# ESP8266-Thing-Dev.net
KiCad netlist of a schematic drawn in EAGLE
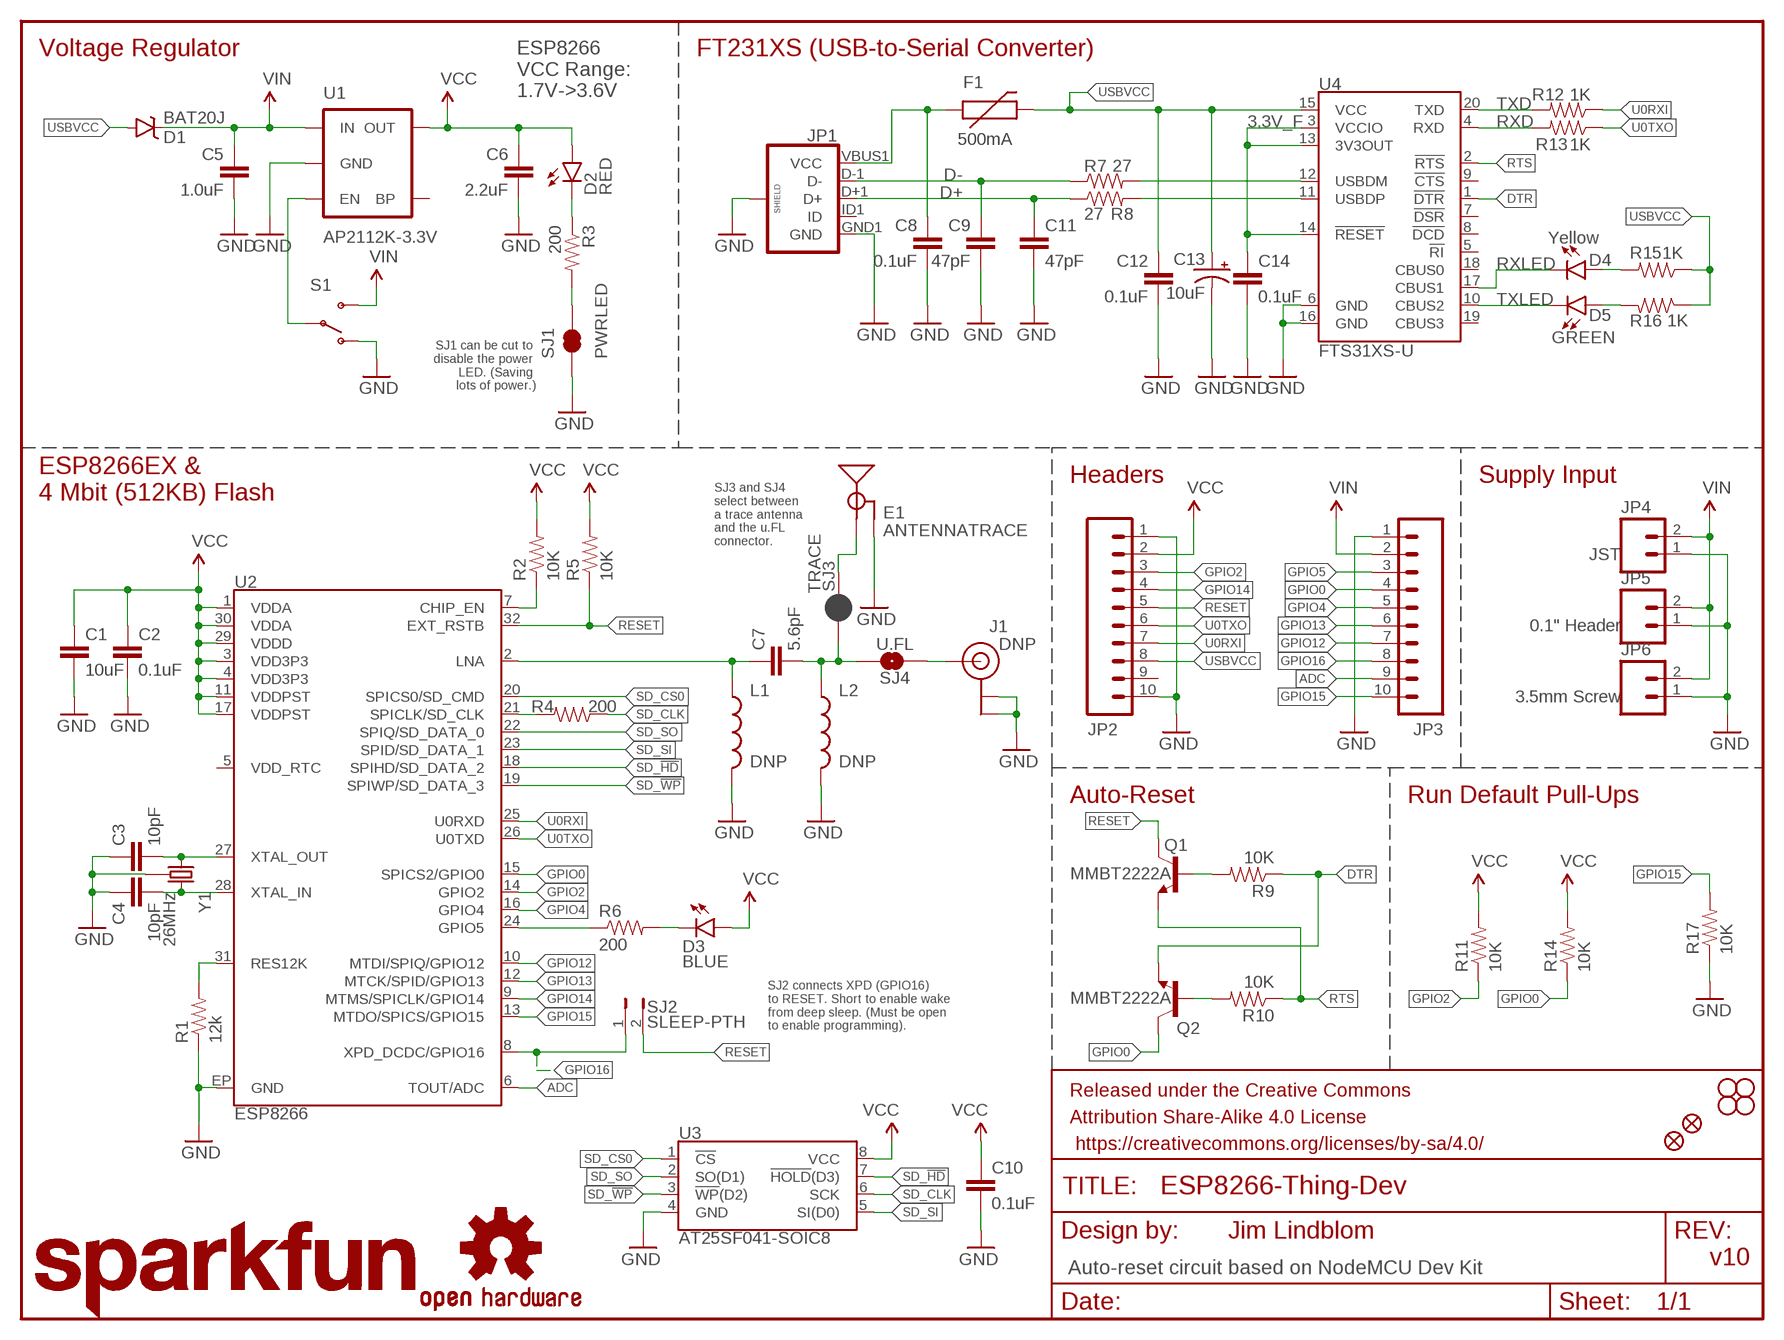
[diagram p0: schematic, sheet 1]

(export (version "E")
  (design (tool "Eeschema 10.0.6"))
  (components
    (comp (ref "C1")
      (value "10uF")
      (footprint "eagle-import:0603-CAP")
      (libsource (lib "eagle-import") (part "10UF-6.3V-20%(0603)"))
    )
    (comp (ref "C2")
      (value "0.1uF")
      (footprint "eagle-import:0603-CAP")
      (libsource (lib "eagle-import") (part "0.1UF-25V(+80/-20%)(0603)"))
    )
    (comp (ref "C3")
      (value "10pF")
      (footprint "eagle-import:0603-CAP")
      (libsource (lib "eagle-import") (part "10PF-50V-5%(0603)"))
    )
    (comp (ref "C4")
      (value "10pF")
      (footprint "eagle-import:0603-CAP")
      (libsource (lib "eagle-import") (part "10PF-50V-5%(0603)"))
    )
    (comp (ref "C5")
      (value "1.0uF")
      (footprint "eagle-import:0805")
      (libsource (lib "eagle-import") (part "1.0UF-25V-+80/-20(0805)"))
    )
    (comp (ref "C6")
      (value "2.2uF")
      (footprint "eagle-import:0603-CAP")
      (libsource (lib "eagle-import") (part "2.2UF-10V-20%(0603)"))
    )
    (comp (ref "C7")
      (value "5.6pF")
      (footprint "eagle-import:0603-CAP")
      (libsource (lib "eagle-import") (part "CAP0603-CAP"))
    )
    (comp (ref "C8")
      (value "0.1uF")
      (footprint "eagle-import:0603-CAP")
      (libsource (lib "eagle-import") (part "0.1UF-25V(+80/-20%)(0603)"))
    )
    (comp (ref "C9")
      (value "47pF")
      (footprint "eagle-import:0603-CAP")
      (libsource (lib "eagle-import") (part "47PF-50V-5%(0603)"))
    )
    (comp (ref "C10")
      (value "0.1uF")
      (footprint "eagle-import:0603-CAP")
      (libsource (lib "eagle-import") (part "0.1UF-25V(+80/-20%)(0603)"))
    )
    (comp (ref "C11")
      (value "47pF")
      (footprint "eagle-import:0603-CAP")
      (libsource (lib "eagle-import") (part "47PF-50V-5%(0603)"))
    )
    (comp (ref "C12")
      (value "0.1uF")
      (footprint "eagle-import:0603-CAP")
      (libsource (lib "eagle-import") (part "0.1UF-25V(+80/-20%)(0603)"))
    )
    (comp (ref "C13")
      (value "10uF")
      (footprint "eagle-import:EIA3216")
      (libsource (lib "eagle-import") (part "10UF-16V-10%(TANT)"))
    )
    (comp (ref "C14")
      (value "0.1uF")
      (footprint "eagle-import:0603-CAP")
      (libsource (lib "eagle-import") (part "0.1UF-25V(+80/-20%)(0603)"))
    )
    (comp (ref "D1")
      (value "BAT20J")
      (footprint "eagle-import:SOD-323")
      (libsource (lib "eagle-import") (part "DIODE-SCHOTTKY-BAT20J"))
    )
    (comp (ref "D2")
      (value "RED")
      (footprint "eagle-import:LED-0603")
      (libsource (lib "eagle-import") (part "LED-RED0603"))
    )
    (comp (ref "D3")
      (value "BLUE")
      (footprint "eagle-import:LED-0603")
      (libsource (lib "eagle-import") (part "LED-BLUE0603"))
    )
    (comp (ref "D4")
      (value "Yellow")
      (footprint "eagle-import:LED-0603")
      (libsource (lib "eagle-import") (part "LED-YELLOW0603"))
    )
    (comp (ref "D5")
      (value "GREEN")
      (footprint "eagle-import:LED-0603")
      (libsource (lib "eagle-import") (part "LED-GREEN0603"))
    )
    (comp (ref "E1")
      (value "ANTENNATRACE")
      (footprint "eagle-import:TRACE_ANTENNA_2.4GHZ_25.7MM")
      (libsource (lib "eagle-import") (part "ANTENNATRACE"))
    )
    (comp (ref "F1")
      (value "500mA")
      (footprint "eagle-import:PTC-1206")
      (libsource (lib "eagle-import") (part "PTCSMD"))
    )
    (comp (ref "FID1")
      (value "FIDUCIAL1X2")
      (footprint "eagle-import:FIDUCIAL-1X2")
      (libsource (lib "eagle-import") (part "FIDUCIAL1X2"))
    )
    (comp (ref "FID2")
      (value "FIDUCIAL1X2")
      (footprint "eagle-import:FIDUCIAL-1X2")
      (libsource (lib "eagle-import") (part "FIDUCIAL1X2"))
    )
    (comp (ref "FRAME1")
      (value "FRAME-LETTER")
      (footprint "eagle-import:CREATIVE_COMMONS")
      (libsource (lib "eagle-import") (part "FRAME-LETTER"))
    )
    (comp (ref "J1")
      (value "DNP")
      (footprint "eagle-import:U.FL")
      (libsource (lib "eagle-import") (part "U.FL"))
    )
    (comp (ref "JP1")
      (value "USB_MICROB_PLUGCONN-11752")
      (footprint "eagle-import:USB-B-MICRO-SMD_V03")
      (libsource (lib "eagle-import") (part "USB_MICROB_PLUGCONN-11752"))
    )
    (comp (ref "JP2")
      (value "M10NO_SILK_PTH_FEMALE")
      (footprint "eagle-import:1X10_NO_SILK")
      (libsource (lib "eagle-import") (part "M10NO_SILK_PTH_FEMALE"))
    )
    (comp (ref "JP3")
      (value "M10NO_SILK_PTH_FEMALE")
      (footprint "eagle-import:1X10_NO_SILK")
      (libsource (lib "eagle-import") (part "M10NO_SILK_PTH_FEMALE"))
    )
    (comp (ref "JP4")
      (value "M02JST-PTH-2")
      (footprint "eagle-import:JST-2-PTH")
      (libsource (lib "eagle-import") (part "M02JST-PTH-2"))
    )
    (comp (ref "JP5")
      (value "M021X02_NO_SILK")
      (footprint "eagle-import:1X02_NO_SILK")
      (libsource (lib "eagle-import") (part "M021X02_NO_SILK"))
    )
    (comp (ref "JP6")
      (value "M023.5MM-NO_SILK")
      (footprint "eagle-import:SCREWTERMINAL-3.5MM-2-NS")
      (libsource (lib "eagle-import") (part "M023.5MM-NO_SILK"))
    )
    (comp (ref "L1")
      (value "DNP")
      (footprint "eagle-import:0603")
      (libsource (lib "eagle-import") (part "INDUCTOR0603"))
    )
    (comp (ref "L2")
      (value "DNP")
      (footprint "eagle-import:0603")
      (libsource (lib "eagle-import") (part "INDUCTOR0603"))
    )
    (comp (ref "LOGO1")
      (value "SFE_LOGO_NAME.2_INCH")
      (footprint "eagle-import:SFE_LOGO_NAME_.2")
      (libsource (lib "eagle-import") (part "SFE_LOGO_NAME.2_INCH"))
    )
    (comp (ref "LOGO2")
      (value "OSHW-LOGOS")
      (footprint "eagle-import:OSHW-LOGO-S")
      (libsource (lib "eagle-import") (part "OSHW-LOGOS"))
    )
    (comp (ref "Q1")
      (value "MMBT2222A")
      (footprint "eagle-import:SOT23-3")
      (libsource (lib "eagle-import") (part "TRANSISTOR_NPNMMBT2222A"))
    )
    (comp (ref "Q2")
      (value "MMBT2222A")
      (footprint "eagle-import:SOT23-3")
      (libsource (lib "eagle-import") (part "TRANSISTOR_NPNMMBT2222A"))
    )
    (comp (ref "R1")
      (value "12k")
      (footprint "eagle-import:0603-RES")
      (libsource (lib "eagle-import") (part "12KOHM-1/10W-1%(0603)"))
    )
    (comp (ref "R2")
      (value "10K")
      (footprint "eagle-import:0603-RES")
      (libsource (lib "eagle-import") (part "10KOHM1/10W1%(0603)0603"))
    )
    (comp (ref "R3")
      (value "200")
      (footprint "eagle-import:0603-RES")
      (libsource (lib "eagle-import") (part "200OHM1/10W1%(0603)"))
    )
    (comp (ref "R4")
      (value "200")
      (footprint "eagle-import:0603-RES")
      (libsource (lib "eagle-import") (part "200OHM1/10W1%(0603)"))
    )
    (comp (ref "R5")
      (value "10K")
      (footprint "eagle-import:0603-RES")
      (libsource (lib "eagle-import") (part "10KOHM1/10W1%(0603)0603"))
    )
    (comp (ref "R6")
      (value "200")
      (footprint "eagle-import:0603-RES")
      (libsource (lib "eagle-import") (part "200OHM1/10W1%(0603)"))
    )
    (comp (ref "R7")
      (value "27")
      (footprint "eagle-import:0603-RES")
      (libsource (lib "eagle-import") (part "27OHM1/10W1%(0603)0603-RES"))
    )
    (comp (ref "R8")
      (value "27")
      (footprint "eagle-import:0603-RES")
      (libsource (lib "eagle-import") (part "27OHM1/10W1%(0603)0603-RES"))
    )
    (comp (ref "R9")
      (value "10K")
      (footprint "eagle-import:0603-RES")
      (libsource (lib "eagle-import") (part "10KOHM1/10W1%(0603)0603"))
    )
    (comp (ref "R10")
      (value "10K")
      (footprint "eagle-import:0603-RES")
      (libsource (lib "eagle-import") (part "10KOHM1/10W1%(0603)0603"))
    )
    (comp (ref "R11")
      (value "10K")
      (footprint "eagle-import:0603-RES")
      (libsource (lib "eagle-import") (part "10KOHM1/10W1%(0603)0603"))
    )
    (comp (ref "R12")
      (value "1K")
      (footprint "eagle-import:0603-RES")
      (libsource (lib "eagle-import") (part "1KOHM-1/10W-1%(0603)"))
    )
    (comp (ref "R13")
      (value "1K")
      (footprint "eagle-import:0603-RES")
      (libsource (lib "eagle-import") (part "1KOHM-1/10W-1%(0603)"))
    )
    (comp (ref "R14")
      (value "10K")
      (footprint "eagle-import:0603-RES")
      (libsource (lib "eagle-import") (part "10KOHM1/10W1%(0603)0603"))
    )
    (comp (ref "R15")
      (value "1K")
      (footprint "eagle-import:0603-RES")
      (libsource (lib "eagle-import") (part "1KOHM-1/10W-1%(0603)"))
    )
    (comp (ref "R16")
      (value "1K")
      (footprint "eagle-import:0603-RES")
      (libsource (lib "eagle-import") (part "1KOHM-1/10W-1%(0603)"))
    )
    (comp (ref "R17")
      (value "10K")
      (footprint "eagle-import:0603-RES")
      (libsource (lib "eagle-import") (part "10KOHM1/10W1%(0603)0603"))
    )
    (comp (ref "S1")
      (value "SWITCH-SPDT-SMD-A")
      (footprint "eagle-import:SWITCH-SPST-SMD-A")
      (libsource (lib "eagle-import") (part "SWITCH-SPDT-SMD-A"))
    )
    (comp (ref "SJ1")
      (value "PWRLED")
      (footprint "eagle-import:PAD-JUMPER-2-NC_BY_TRACE_YES_SILK")
      (libsource (lib "eagle-import") (part "JUMPER-PAD-2-NC_BY_TRACE"))
    )
    (comp (ref "SJ2")
      (value "SLEEP-PTH")
      (footprint "eagle-import:PTH-JUMPER-2-NO_NO_SILK")
      (libsource (lib "eagle-import") (part "JUMPER-PTH-2-NO"))
    )
    (comp (ref "SJ3")
      (value "TRACE")
      (footprint "eagle-import:PAD-JUMPER-2-NC_BY_PASTE_NO_SILK")
      (libsource (lib "eagle-import") (part "JUMPER-PAD-2-NC_BY_PASTENO-SILK"))
    )
    (comp (ref "SJ4")
      (value "U.FL")
      (footprint "eagle-import:PAD-JUMPER-2-NO_NO_SILK")
      (libsource (lib "eagle-import") (part "JUMPER-PAD-2-NO"))
    )
    (comp (ref "STANDOFF1")
      (value "STAND-OFF")
      (footprint "eagle-import:STAND-OFF")
      (libsource (lib "eagle-import") (part "STAND-OFF"))
    )
    (comp (ref "STANDOFF2")
      (value "STAND-OFF")
      (footprint "eagle-import:STAND-OFF")
      (libsource (lib "eagle-import") (part "STAND-OFF"))
    )
    (comp (ref "STANDOFF3")
      (value "STAND-OFF")
      (footprint "eagle-import:STAND-OFF")
      (libsource (lib "eagle-import") (part "STAND-OFF"))
    )
    (comp (ref "STANDOFF4")
      (value "STAND-OFF")
      (footprint "eagle-import:STAND-OFF")
      (libsource (lib "eagle-import") (part "STAND-OFF"))
    )
    (comp (ref "U1")
      (value "AP2112K-3.3V")
      (footprint "eagle-import:SOT23-5")
      (libsource (lib "eagle-import") (part "V_REG_LDOSMD"))
    )
    (comp (ref "U2")
      (value "ESP8266")
      (footprint "eagle-import:QFN32")
      (libsource (lib "eagle-import") (part "ESP8266"))
    )
    (comp (ref "U3")
      (value "AT25SF041-SOIC8")
      (footprint "eagle-import:SO08")
      (libsource (lib "eagle-import") (part "AT25SF041-SOIC8"))
    )
    (comp (ref "U4")
      (value "FTS31XS-U")
      (footprint "eagle-import:SSOP20_L")
      (libsource (lib "eagle-import") (part "FT231XS"))
    )
    (comp (ref "Y1")
      (value "26MHz")
      (footprint "eagle-import:CRYSTAL-SMD-3.2X2.5")
      (libsource (lib "eagle-import") (part "CRYSTAL-GROUNDED3.2X2.5"))
    )
  )
  (nets
    (net (code "1") (name "/3.3V_F") (class "Default")
      (node (ref "C14") (pin "1") (pinfunction "1_1") (pintype "passive"))
      (node (ref "U4") (pin "13") (pinfunction "3V3OUT_13") (pintype "bidirectional"))
      (node (ref "U4") (pin "14") (pinfunction "~{RESET}_14") (pintype "bidirectional"))
      (node (ref "U4") (pin "3") (pinfunction "VCCIO_3") (pintype "bidirectional"))
    )
    (net (code "2") (name "/D+") (class "Default")
      (node (ref "C11") (pin "1") (pinfunction "1_1") (pintype "passive"))
      (node (ref "JP1") (pin "D+1") (pinfunction "D+_D+1") (pintype "bidirectional"))
      (node (ref "R8") (pin "1") (pinfunction "1_1") (pintype "passive"))
    )
    (net (code "3") (name "/D-") (class "Default")
      (node (ref "C9") (pin "1") (pinfunction "1_1") (pintype "passive"))
      (node (ref "JP1") (pin "D-1") (pinfunction "D-_D-1") (pintype "bidirectional"))
      (node (ref "R7") (pin "1") (pinfunction "1_1") (pintype "passive"))
    )
    (net (code "4") (name "/RXD") (class "Default")
      (node (ref "R13") (pin "2") (pinfunction "2_2") (pintype "passive"))
      (node (ref "U4") (pin "4") (pinfunction "RXD_4") (pintype "bidirectional"))
    )
    (net (code "5") (name "/RXLED") (class "Default")
      (node (ref "D4") (pin "C") (pinfunction "C_C") (pintype "passive"))
      (node (ref "U4") (pin "17") (pinfunction "CBUS1_17") (pintype "bidirectional"))
    )
    (net (code "6") (name "/SD_~{HD}") (class "Default")
      (node (ref "U2") (pin "18") (pinfunction "SPIHD/SD_DATA_2_18") (pintype "bidirectional"))
      (node (ref "U3") (pin "7") (pinfunction "~{HOLD}(D3)_7") (pintype "bidirectional"))
    )
    (net (code "7") (name "/SD_~{WP}") (class "Default")
      (node (ref "U2") (pin "19") (pinfunction "SPIWP/SD_DATA_3_19") (pintype "bidirectional"))
      (node (ref "U3") (pin "3") (pinfunction "~{WP}(D2)_3") (pintype "bidirectional"))
    )
    (net (code "8") (name "/TXD") (class "Default")
      (node (ref "R12") (pin "2") (pinfunction "2_2") (pintype "passive"))
      (node (ref "U4") (pin "20") (pinfunction "TXD_20") (pintype "bidirectional"))
    )
    (net (code "9") (name "/TXLED") (class "Default")
      (node (ref "D5") (pin "C") (pinfunction "C_C") (pintype "passive"))
      (node (ref "U4") (pin "10") (pinfunction "CBUS2_10") (pintype "bidirectional"))
    )
    (net (code "10") (name "ADC") (class "Default")
      (node (ref "JP3") (pin "9") (pinfunction "9_9") (pintype "passive"))
      (node (ref "U2") (pin "6") (pinfunction "TOUT/ADC_6") (pintype "bidirectional"))
    )
    (net (code "11") (name "DTR") (class "Default")
      (node (ref "Q2") (pin "2") (pinfunction "E_2") (pintype "passive"))
      (node (ref "R9") (pin "1") (pinfunction "1_1") (pintype "passive"))
      (node (ref "U4") (pin "1") (pinfunction "~{DTR}_1") (pintype "bidirectional"))
    )
    (net (code "12") (name "GND") (class "Default")
      (node (ref "C1") (pin "2") (pinfunction "2_2") (pintype "passive"))
      (node (ref "C10") (pin "2") (pinfunction "2_2") (pintype "passive"))
      (node (ref "C11") (pin "2") (pinfunction "2_2") (pintype "passive"))
      (node (ref "C12") (pin "2") (pinfunction "2_2") (pintype "passive"))
      (node (ref "C13") (pin "C") (pinfunction "-_C") (pintype "passive"))
      (node (ref "C14") (pin "2") (pinfunction "2_2") (pintype "passive"))
      (node (ref "C2") (pin "2") (pinfunction "2_2") (pintype "passive"))
      (node (ref "C3") (pin "1") (pinfunction "1_1") (pintype "passive"))
      (node (ref "C4") (pin "1") (pinfunction "1_1") (pintype "passive"))
      (node (ref "C5") (pin "2") (pinfunction "2_2") (pintype "passive"))
      (node (ref "C6") (pin "2") (pinfunction "2_2") (pintype "passive"))
      (node (ref "C8") (pin "2") (pinfunction "2_2") (pintype "passive"))
      (node (ref "C9") (pin "2") (pinfunction "2_2") (pintype "passive"))
      (node (ref "E1") (pin "GND") (pinfunction "GND_GND") (pintype "bidirectional"))
      (node (ref "E1") (pin "GND2") (pinfunction "GND_GND2") (pintype "bidirectional"))
      (node (ref "J1") (pin "P$1") (pinfunction "GND_P$1") (pintype "bidirectional"))
      (node (ref "J1") (pin "P$2") (pinfunction "GND_P$2") (pintype "bidirectional"))
      (node (ref "JP1") (pin "GND1") (pinfunction "GND_GND1") (pintype "bidirectional"))
      (node (ref "JP1") (pin "SHIELD1") (pinfunction "SHIELD_SHIELD1") (pintype "bidirectional"))
      (node (ref "JP1") (pin "SHIELD2") (pinfunction "SHIELD_SHIELD2") (pintype "bidirectional"))
      (node (ref "JP1") (pin "SHIELD3") (pinfunction "SHIELD_SHIELD3") (pintype "bidirectional"))
      (node (ref "JP2") (pin "1") (pinfunction "1_1") (pintype "passive"))
      (node (ref "JP2") (pin "10") (pinfunction "10_10") (pintype "passive"))
      (node (ref "JP3") (pin "1") (pinfunction "1_1") (pintype "passive"))
      (node (ref "JP4") (pin "1") (pinfunction "1_1") (pintype "passive"))
      (node (ref "JP5") (pin "1") (pinfunction "1_1") (pintype "passive"))
      (node (ref "JP6") (pin "1") (pinfunction "1_1") (pintype "passive"))
      (node (ref "L1") (pin "2") (pinfunction "2_2") (pintype "passive"))
      (node (ref "L2") (pin "2") (pinfunction "2_2") (pintype "passive"))
      (node (ref "R1") (pin "1") (pinfunction "1_1") (pintype "passive"))
      (node (ref "R17") (pin "1") (pinfunction "1_1") (pintype "passive"))
      (node (ref "S1") (pin "1") (pinfunction "O_1") (pintype "passive"))
      (node (ref "SJ1") (pin "1") (pinfunction "1_1") (pintype "passive"))
      (node (ref "U1") (pin "2") (pinfunction "GND_2") (pintype "input"))
      (node (ref "U2") (pin "EP") (pinfunction "GND_EP") (pintype "bidirectional"))
      (node (ref "U3") (pin "4") (pinfunction "GND_4") (pintype "bidirectional"))
      (node (ref "U4") (pin "16") (pinfunction "GND_16") (pintype "bidirectional"))
      (node (ref "U4") (pin "6") (pinfunction "GND_6") (pintype "bidirectional"))
      (node (ref "Y1") (pin "2") (pinfunction "GND_2") (pintype "passive"))
      (node (ref "Y1") (pin "4") (pinfunction "GND_4") (pintype "passive"))
    )
    (net (code "13") (name "GPIO0") (class "Default")
      (node (ref "JP3") (pin "4") (pinfunction "4_4") (pintype "passive"))
      (node (ref "Q2") (pin "3") (pinfunction "C_3") (pintype "passive"))
      (node (ref "R14") (pin "1") (pinfunction "1_1") (pintype "passive"))
      (node (ref "U2") (pin "15") (pinfunction "SPICS2/GPIO0_15") (pintype "bidirectional"))
    )
    (net (code "14") (name "GPIO2") (class "Default")
      (node (ref "JP2") (pin "3") (pinfunction "3_3") (pintype "passive"))
      (node (ref "R11") (pin "1") (pinfunction "1_1") (pintype "passive"))
      (node (ref "U2") (pin "14") (pinfunction "GPIO2_14") (pintype "bidirectional"))
    )
    (net (code "15") (name "GPIO4") (class "Default")
      (node (ref "JP3") (pin "5") (pinfunction "5_5") (pintype "passive"))
      (node (ref "U2") (pin "16") (pinfunction "GPIO4_16") (pintype "bidirectional"))
    )
    (net (code "16") (name "GPIO5") (class "Default")
      (node (ref "JP3") (pin "3") (pinfunction "3_3") (pintype "passive"))
      (node (ref "R6") (pin "1") (pinfunction "1_1") (pintype "passive"))
      (node (ref "U2") (pin "24") (pinfunction "GPIO5_24") (pintype "bidirectional"))
    )
    (net (code "17") (name "GPIO12") (class "Default")
      (node (ref "JP3") (pin "7") (pinfunction "7_7") (pintype "passive"))
      (node (ref "U2") (pin "10") (pinfunction "MTDI/SPIQ/GPIO12_10") (pintype "bidirectional"))
    )
    (net (code "18") (name "GPIO13") (class "Default")
      (node (ref "JP3") (pin "6") (pinfunction "6_6") (pintype "passive"))
      (node (ref "U2") (pin "12") (pinfunction "MTCK/SPID/GPIO13_12") (pintype "bidirectional"))
    )
    (net (code "19") (name "GPIO14") (class "Default")
      (node (ref "JP2") (pin "4") (pinfunction "4_4") (pintype "passive"))
      (node (ref "U2") (pin "9") (pinfunction "MTMS/SPICLK/GPIO14_9") (pintype "bidirectional"))
    )
    (net (code "20") (name "GPIO15") (class "Default")
      (node (ref "JP3") (pin "10") (pinfunction "10_10") (pintype "passive"))
      (node (ref "R17") (pin "2") (pinfunction "2_2") (pintype "passive"))
      (node (ref "U2") (pin "13") (pinfunction "MTDO/SPICS/GPIO15_13") (pintype "bidirectional"))
    )
    (net (code "21") (name "GPIO16") (class "Default")
      (node (ref "JP3") (pin "8") (pinfunction "8_8") (pintype "passive"))
      (node (ref "SJ2") (pin "1") (pinfunction "1_1") (pintype "passive"))
      (node (ref "U2") (pin "8") (pinfunction "XPD_DCDC/GPIO16_8") (pintype "bidirectional"))
    )
    (net (code "22") (name "Net-(C7-Pad2)") (class "Default")
      (node (ref "C7") (pin "2") (pinfunction "2_2") (pintype "passive"))
      (node (ref "L2") (pin "1") (pinfunction "1_1") (pintype "passive"))
      (node (ref "SJ3") (pin "1") (pinfunction "1_1") (pintype "passive"))
      (node (ref "SJ4") (pin "2") (pinfunction "2_2") (pintype "passive"))
    )
    (net (code "23") (name "Net-(D2-PadC)") (class "Default")
      (node (ref "D2") (pin "C") (pinfunction "C_C") (pintype "passive"))
      (node (ref "R3") (pin "1") (pinfunction "1_1") (pintype "passive"))
    )
    (net (code "24") (name "Net-(D3-PadC)") (class "Default")
      (node (ref "D3") (pin "C") (pinfunction "C_C") (pintype "passive"))
      (node (ref "R6") (pin "2") (pinfunction "2_2") (pintype "passive"))
    )
    (net (code "25") (name "Net-(D4-PadA)") (class "Default")
      (node (ref "D4") (pin "A") (pinfunction "A_A") (pintype "passive"))
      (node (ref "R15") (pin "2") (pinfunction "2_2") (pintype "passive"))
    )
    (net (code "26") (name "Net-(D5-PadA)") (class "Default")
      (node (ref "D5") (pin "A") (pinfunction "A_A") (pintype "passive"))
      (node (ref "R16") (pin "2") (pinfunction "2_2") (pintype "passive"))
    )
    (net (code "27") (name "Net-(E1-SIGNAL)") (class "Default")
      (node (ref "E1") (pin "ANT") (pinfunction "SIGNAL_ANT") (pintype "bidirectional"))
      (node (ref "SJ3") (pin "2") (pinfunction "2_2") (pintype "passive"))
    )
    (net (code "28") (name "Net-(J1-SIGNAL)") (class "Default")
      (node (ref "J1") (pin "P$3") (pinfunction "SIGNAL_P$3") (pintype "bidirectional"))
      (node (ref "SJ4") (pin "1") (pinfunction "1_1") (pintype "passive"))
    )
    (net (code "29") (name "Net-(JP1-VCC)") (class "Default")
      (node (ref "C8") (pin "1") (pinfunction "1_1") (pintype "passive"))
      (node (ref "F1") (pin "1") (pinfunction "1_1") (pintype "bidirectional"))
      (node (ref "JP1") (pin "VBUS1") (pinfunction "VCC_VBUS1") (pintype "bidirectional"))
    )
    (net (code "30") (name "Net-(Q1-B)") (class "Default")
      (node (ref "Q1") (pin "1") (pinfunction "B_1") (pintype "passive"))
      (node (ref "R9") (pin "2") (pinfunction "2_2") (pintype "passive"))
    )
    (net (code "31") (name "Net-(Q2-B)") (class "Default")
      (node (ref "Q2") (pin "1") (pinfunction "B_1") (pintype "passive"))
      (node (ref "R10") (pin "2") (pinfunction "2_2") (pintype "passive"))
    )
    (net (code "32") (name "Net-(R3-Pad2)") (class "Default")
      (node (ref "R3") (pin "2") (pinfunction "2_2") (pintype "passive"))
      (node (ref "SJ1") (pin "2") (pinfunction "2_2") (pintype "passive"))
    )
    (net (code "33") (name "Net-(S1-P)") (class "Default")
      (node (ref "S1") (pin "2") (pinfunction "P_2") (pintype "passive"))
      (node (ref "U1") (pin "3") (pinfunction "EN_3") (pintype "input"))
    )
    (net (code "34") (name "Net-(U2-CHIP_EN)") (class "Default")
      (node (ref "R2") (pin "1") (pinfunction "1_1") (pintype "passive"))
      (node (ref "U2") (pin "7") (pinfunction "CHIP_EN_7") (pintype "bidirectional"))
    )
    (net (code "35") (name "Net-(U2-LNA)") (class "Default")
      (node (ref "C7") (pin "1") (pinfunction "1_1") (pintype "passive"))
      (node (ref "L1") (pin "1") (pinfunction "1_1") (pintype "passive"))
      (node (ref "U2") (pin "2") (pinfunction "LNA_2") (pintype "bidirectional"))
    )
    (net (code "36") (name "Net-(U2-RES12K)") (class "Default")
      (node (ref "R1") (pin "2") (pinfunction "2_2") (pintype "passive"))
      (node (ref "U2") (pin "31") (pinfunction "RES12K_31") (pintype "bidirectional"))
    )
    (net (code "37") (name "Net-(U2-SPICLK{slash}SD_CLK)") (class "Default")
      (node (ref "R4") (pin "2") (pinfunction "2_2") (pintype "passive"))
      (node (ref "U2") (pin "21") (pinfunction "SPICLK/SD_CLK_21") (pintype "bidirectional"))
    )
    (net (code "38") (name "Net-(U2-XTAL_IN)") (class "Default")
      (node (ref "C4") (pin "2") (pinfunction "2_2") (pintype "passive"))
      (node (ref "U2") (pin "28") (pinfunction "XTAL_IN_28") (pintype "bidirectional"))
      (node (ref "Y1") (pin "3") (pinfunction "2_3") (pintype "passive"))
    )
    (net (code "39") (name "Net-(U2-XTAL_OUT)") (class "Default")
      (node (ref "C3") (pin "2") (pinfunction "2_2") (pintype "passive"))
      (node (ref "U2") (pin "27") (pinfunction "XTAL_OUT_27") (pintype "bidirectional"))
      (node (ref "Y1") (pin "1") (pinfunction "1_1") (pintype "passive"))
    )
    (net (code "40") (name "Net-(U4-USBDM)") (class "Default")
      (node (ref "R7") (pin "2") (pinfunction "2_2") (pintype "passive"))
      (node (ref "U4") (pin "12") (pinfunction "USBDM_12") (pintype "bidirectional"))
    )
    (net (code "41") (name "Net-(U4-USBDP)") (class "Default")
      (node (ref "R8") (pin "2") (pinfunction "2_2") (pintype "passive"))
      (node (ref "U4") (pin "11") (pinfunction "USBDP_11") (pintype "bidirectional"))
    )
    (net (code "42") (name "RESET") (class "Default")
      (node (ref "JP2") (pin "5") (pinfunction "5_5") (pintype "passive"))
      (node (ref "Q1") (pin "3") (pinfunction "C_3") (pintype "passive"))
      (node (ref "R5") (pin "1") (pinfunction "1_1") (pintype "passive"))
      (node (ref "SJ2") (pin "2") (pinfunction "2_2") (pintype "passive"))
      (node (ref "U2") (pin "32") (pinfunction "EXT_RSTB_32") (pintype "bidirectional"))
    )
    (net (code "43") (name "RTS") (class "Default")
      (node (ref "Q1") (pin "2") (pinfunction "E_2") (pintype "passive"))
      (node (ref "R10") (pin "1") (pinfunction "1_1") (pintype "passive"))
      (node (ref "U4") (pin "2") (pinfunction "~{RTS}_2") (pintype "bidirectional"))
    )
    (net (code "44") (name "SD_CLK") (class "Default")
      (node (ref "R4") (pin "1") (pinfunction "1_1") (pintype "passive"))
      (node (ref "U3") (pin "6") (pinfunction "SCK_6") (pintype "bidirectional"))
    )
    (net (code "45") (name "SD_CS0") (class "Default")
      (node (ref "U2") (pin "20") (pinfunction "SPICS0/SD_CMD_20") (pintype "bidirectional"))
      (node (ref "U3") (pin "1") (pinfunction "~{CS}_1") (pintype "bidirectional"))
    )
    (net (code "46") (name "SD_SI") (class "Default")
      (node (ref "U2") (pin "23") (pinfunction "SPID/SD_DATA_1_23") (pintype "bidirectional"))
      (node (ref "U3") (pin "5") (pinfunction "SI(D0)_5") (pintype "bidirectional"))
    )
    (net (code "47") (name "SD_SO") (class "Default")
      (node (ref "U2") (pin "22") (pinfunction "SPIQ/SD_DATA_0_22") (pintype "bidirectional"))
      (node (ref "U3") (pin "2") (pinfunction "SO(D1)_2") (pintype "bidirectional"))
    )
    (net (code "48") (name "U0RXI") (class "Default")
      (node (ref "JP2") (pin "7") (pinfunction "7_7") (pintype "passive"))
      (node (ref "R12") (pin "1") (pinfunction "1_1") (pintype "passive"))
      (node (ref "U2") (pin "25") (pinfunction "U0RXD_25") (pintype "bidirectional"))
    )
    (net (code "49") (name "U0TXO") (class "Default")
      (node (ref "JP2") (pin "6") (pinfunction "6_6") (pintype "passive"))
      (node (ref "R13") (pin "1") (pinfunction "1_1") (pintype "passive"))
      (node (ref "U2") (pin "26") (pinfunction "U0TXD_26") (pintype "bidirectional"))
    )
    (net (code "50") (name "USBVCC") (class "Default")
      (node (ref "C12") (pin "1") (pinfunction "1_1") (pintype "passive"))
      (node (ref "C13") (pin "A") (pinfunction "+_A") (pintype "passive"))
      (node (ref "D1") (pin "A") (pinfunction "A_A") (pintype "passive"))
      (node (ref "F1") (pin "2") (pinfunction "2_2") (pintype "bidirectional"))
      (node (ref "JP2") (pin "8") (pinfunction "8_8") (pintype "passive"))
      (node (ref "R15") (pin "1") (pinfunction "1_1") (pintype "passive"))
      (node (ref "R16") (pin "1") (pinfunction "1_1") (pintype "passive"))
      (node (ref "U4") (pin "15") (pinfunction "VCC_15") (pintype "bidirectional"))
    )
    (net (code "51") (name "VCC") (class "Default")
      (node (ref "C1") (pin "1") (pinfunction "1_1") (pintype "passive"))
      (node (ref "C10") (pin "1") (pinfunction "1_1") (pintype "passive"))
      (node (ref "C2") (pin "1") (pinfunction "1_1") (pintype "passive"))
      (node (ref "C6") (pin "1") (pinfunction "1_1") (pintype "passive"))
      (node (ref "D2") (pin "A") (pinfunction "A_A") (pintype "passive"))
      (node (ref "D3") (pin "A") (pinfunction "A_A") (pintype "passive"))
      (node (ref "JP2") (pin "2") (pinfunction "2_2") (pintype "passive"))
      (node (ref "R11") (pin "2") (pinfunction "2_2") (pintype "passive"))
      (node (ref "R14") (pin "2") (pinfunction "2_2") (pintype "passive"))
      (node (ref "R2") (pin "2") (pinfunction "2_2") (pintype "passive"))
      (node (ref "R5") (pin "2") (pinfunction "2_2") (pintype "passive"))
      (node (ref "U1") (pin "5") (pinfunction "OUT_5") (pintype "passive"))
      (node (ref "U2") (pin "1") (pinfunction "VDDA_1") (pintype "bidirectional"))
      (node (ref "U2") (pin "11") (pinfunction "VDDPST_11") (pintype "bidirectional"))
      (node (ref "U2") (pin "17") (pinfunction "VDDPST_17") (pintype "bidirectional"))
      (node (ref "U2") (pin "29") (pinfunction "VDDD_29") (pintype "bidirectional"))
      (node (ref "U2") (pin "3") (pinfunction "VDD3P3_3") (pintype "bidirectional"))
      (node (ref "U2") (pin "30") (pinfunction "VDDA_30") (pintype "bidirectional"))
      (node (ref "U2") (pin "4") (pinfunction "VDD3P3_4") (pintype "bidirectional"))
      (node (ref "U3") (pin "8") (pinfunction "VCC_8") (pintype "bidirectional"))
    )
    (net (code "52") (name "VIN") (class "Default")
      (node (ref "C5") (pin "1") (pinfunction "1_1") (pintype "passive"))
      (node (ref "D1") (pin "C") (pinfunction "C_C") (pintype "passive"))
      (node (ref "JP3") (pin "2") (pinfunction "2_2") (pintype "passive"))
      (node (ref "JP4") (pin "2") (pinfunction "2_2") (pintype "passive"))
      (node (ref "JP5") (pin "2") (pinfunction "2_2") (pintype "passive"))
      (node (ref "JP6") (pin "2") (pinfunction "2_2") (pintype "passive"))
      (node (ref "S1") (pin "3") (pinfunction "S_3") (pintype "passive"))
      (node (ref "U1") (pin "1") (pinfunction "IN_1") (pintype "input"))
    )
    (net (code "53") (name "unconnected-(JP1-ID-PadID1)") (class "Default")
      (node (ref "JP1") (pin "ID1") (pinfunction "ID_ID1") (pintype "bidirectional"))
    )
    (net (code "54") (name "unconnected-(JP2-Pad9)") (class "Default")
      (node (ref "JP2") (pin "9") (pinfunction "9_9") (pintype "passive"))
    )
    (net (code "55") (name "unconnected-(U1-BP-Pad4)") (class "Default")
      (node (ref "U1") (pin "4") (pinfunction "BP_4") (pintype "input"))
    )
    (net (code "56") (name "unconnected-(U2-VDD_RTC-Pad5)") (class "Default")
      (node (ref "U2") (pin "5") (pinfunction "VDD_RTC_5") (pintype "bidirectional"))
    )
    (net (code "57") (name "unconnected-(U4-CBUS0-Pad18)") (class "Default")
      (node (ref "U4") (pin "18") (pinfunction "CBUS0_18") (pintype "bidirectional"))
    )
    (net (code "58") (name "unconnected-(U4-CBUS3-Pad19)") (class "Default")
      (node (ref "U4") (pin "19") (pinfunction "CBUS3_19") (pintype "bidirectional"))
    )
    (net (code "59") (name "unconnected-(U4-~{CTS}-Pad9)") (class "Default")
      (node (ref "U4") (pin "9") (pinfunction "~{CTS}_9") (pintype "bidirectional"))
    )
    (net (code "60") (name "unconnected-(U4-~{DCD}-Pad8)") (class "Default")
      (node (ref "U4") (pin "8") (pinfunction "~{DCD}_8") (pintype "bidirectional"))
    )
    (net (code "61") (name "unconnected-(U4-~{DSR}-Pad7)") (class "Default")
      (node (ref "U4") (pin "7") (pinfunction "~{DSR}_7") (pintype "bidirectional"))
    )
    (net (code "62") (name "unconnected-(U4-~{RI}-Pad5)") (class "Default")
      (node (ref "U4") (pin "5") (pinfunction "~{RI}_5") (pintype "bidirectional"))
    )
  )
)
